# Test1.net
KiCad netlist of a schematic drawn in Altium Designer
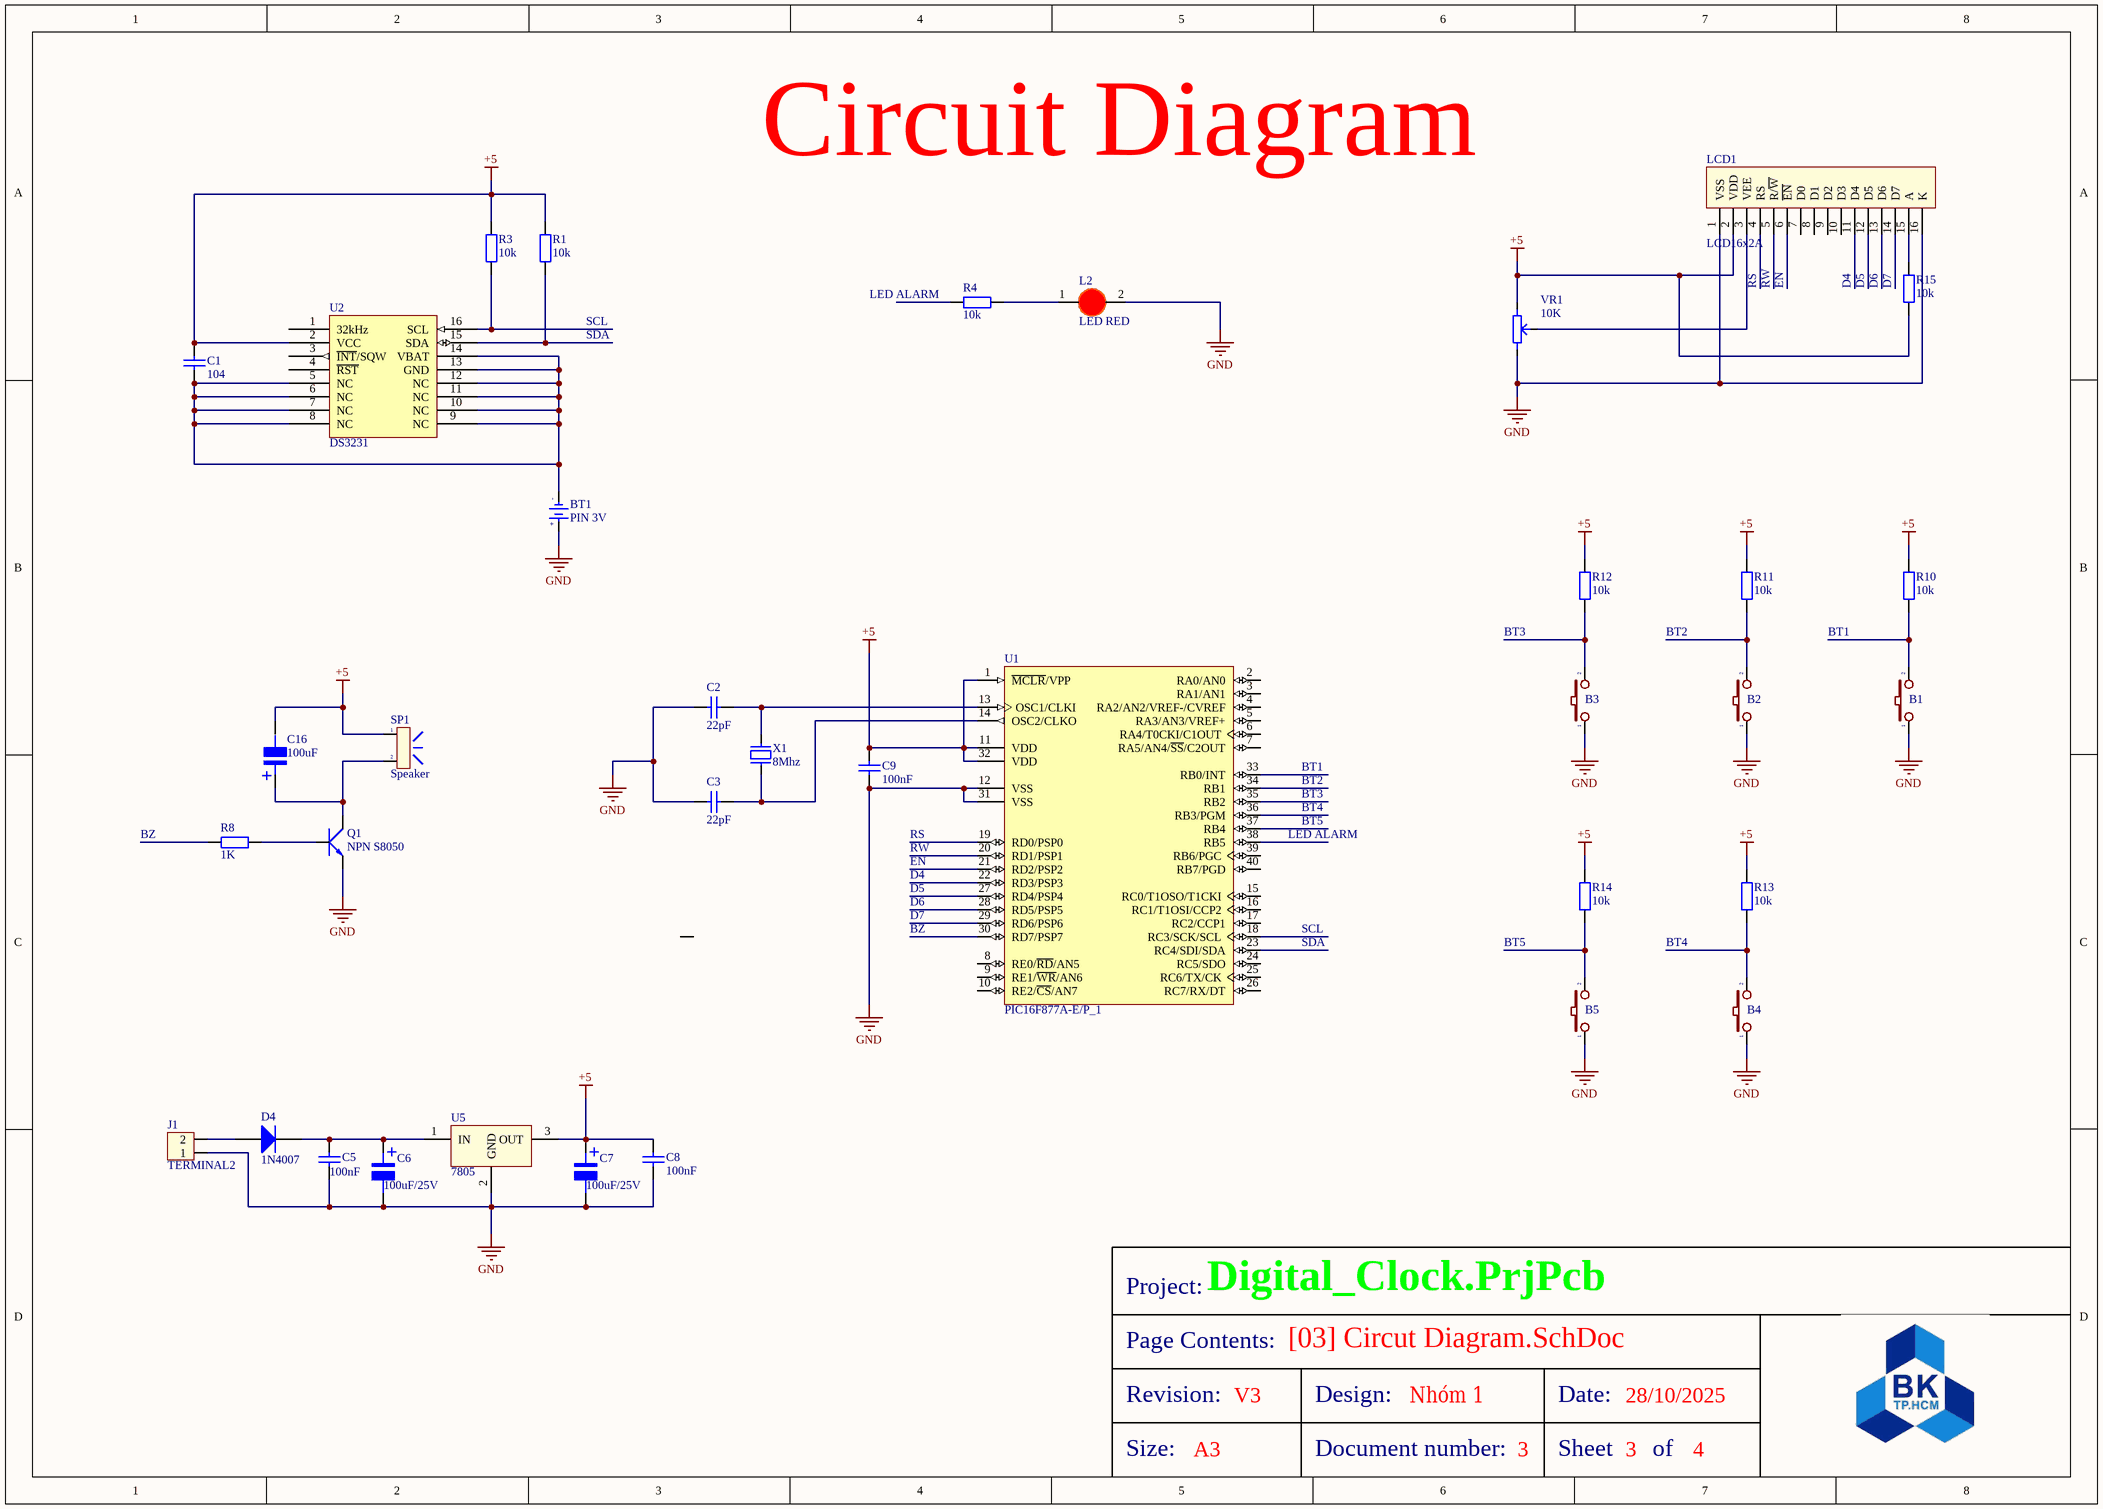
[diagram p0: Test1.SchDoc]

(export (version "E")
  (design (tool "Eeschema 10.0.6"))
  (components
    (comp (ref "B1")
      (value "~")
      (footprint "SW2")
      (description "Switch button 2 pin")
      (libsource (lib "syhaunguyen") (part "SW2"))
    )
    (comp (ref "B2")
      (value "~")
      (footprint "SW2")
      (description "Switch button 2 pin")
      (libsource (lib "syhaunguyen") (part "SW2"))
    )
    (comp (ref "B3")
      (value "~")
      (footprint "SW2")
      (description "Switch button 2 pin")
      (libsource (lib "syhaunguyen") (part "SW2"))
    )
    (comp (ref "B4")
      (value "~")
      (footprint "SW2")
      (description "Switch button 2 pin")
      (libsource (lib "syhaunguyen") (part "SW2"))
    )
    (comp (ref "B5")
      (value "~")
      (footprint "SW2")
      (description "Switch button 2 pin")
      (libsource (lib "syhaunguyen") (part "SW2"))
    )
    (comp (ref "BT1")
      (value "PIN 3V")
      (footprint "PIN3V")
      (description "Battery 3VDC")
      (libsource (lib "syhaunguyen") (part "PIN 3V"))
    )
    (comp (ref "C1")
      (value "104")
      (footprint "tu gom")
      (description "Cắm")
      (libsource (lib "Capacitor") (part "Tu gom 104 50V"))
    )
    (comp (ref "C2")
      (value "22pF")
      (footprint "tu gom")
      (description "Cắm")
      (libsource (lib "Capacitor") (part "Tu gom 22pF 50V"))
    )
    (comp (ref "C3")
      (value "22pF")
      (footprint "tu gom")
      (description "Cắm")
      (libsource (lib "Capacitor") (part "Tu gom 22pF 50V"))
    )
    (comp (ref "C5")
      (value "100nF")
      (footprint "tu gom")
      (description "Cắm")
      (libsource (lib "Capacitor") (part "Tu gom 22pF 50V"))
    )
    (comp (ref "C6")
      (value "100uF/25V")
      (footprint "tu nhom 10 (g)")
      (description "Dán")
      (libsource (lib "") (part "Tu Nhom 100uF 35V_1"))
    )
    (comp (ref "C7")
      (value "100uF/25V")
      (footprint "tu nhom 10 (g)")
      (description "Dán")
      (libsource (lib "") (part "Tu Nhom 100uF 35V_1"))
    )
    (comp (ref "C8")
      (value "100nF")
      (footprint "tu gom")
      (description "Cắm")
      (libsource (lib "Capacitor") (part "Tu gom 22pF 50V"))
    )
    (comp (ref "C9")
      (value "100nF")
      (footprint "tu gom")
      (description "Cắm")
      (libsource (lib "Capacitor") (part "Tu gom 22pF 50V"))
    )
    (comp (ref "C16")
      (value "100uF")
      (footprint "tu nhom 10 (g)")
      (description "Dán")
      (libsource (lib "Capacitor") (part "Tu Nhom 100uF 35V"))
    )
    (comp (ref "D4")
      (value "1N4007")
      (footprint "DIODE SOD-123")
      (description "Dán")
      (libsource (lib "Diode") (part "Diode S4"))
    )
    (comp (ref "J1")
      (value "TERMINAL2")
      (footprint "Header 2P DC 2.54")
      (description "Cắm")
      (libsource (lib "Header") (part "Header 2P 2.54 Duc Cong"))
    )
    (comp (ref "L2")
      (value "LED RED")
      (footprint "LED-5MM-RED")
      (description "Cắm")
      (libsource (lib "Led") (part "LED 5mm Do"))
    )
    (comp (ref "LCD1")
      (value "LCD16x2A")
      (footprint "LCD16X2")
      (description "LCD dipslay 16 char, 2 line")
      (libsource (lib "syhaunguyen") (part "LCD16x2"))
    )
    (comp (ref "Q1")
      (value "NPN S8050")
      (footprint "QTO-92")
      (description "P 600mW, ECB")
      (libsource (lib "syhaunguyen") (part "NPN_ECB"))
    )
    (comp (ref "R1")
      (value "10k")
      (footprint "tro smd 0603")
      (description "Dán")
      (libsource (lib "Resistor") (part "Tro 0603 5% 10k"))
    )
    (comp (ref "R3")
      (value "10k")
      (footprint "tro smd 0603")
      (description "Dán")
      (libsource (lib "Resistor") (part "Tro 0603 5% 10k"))
    )
    (comp (ref "R4")
      (value "10k")
      (footprint "tro smd 0603")
      (description "Dán")
      (libsource (lib "Resistor") (part "Tro 0603 5% 10k"))
    )
    (comp (ref "R8")
      (value "1K")
      (footprint "tro smd 0603")
      (description "Dán")
      (libsource (lib "Resistor") (part "Tro 0603 5% 10k"))
    )
    (comp (ref "R10")
      (value "10k")
      (footprint "tro smd 0603")
      (description "Dán")
      (libsource (lib "Resistor") (part "Tro 0603 5% 10k"))
    )
    (comp (ref "R11")
      (value "10k")
      (footprint "tro smd 0603")
      (description "Dán")
      (libsource (lib "Resistor") (part "Tro 0603 5% 10k"))
    )
    (comp (ref "R12")
      (value "10k")
      (footprint "tro smd 0603")
      (description "Dán")
      (libsource (lib "Resistor") (part "Tro 0603 5% 10k"))
    )
    (comp (ref "R13")
      (value "10k")
      (footprint "tro smd 0603")
      (description "Dán")
      (libsource (lib "Resistor") (part "Tro 0603 5% 10k"))
    )
    (comp (ref "R14")
      (value "10k")
      (footprint "tro smd 0603")
      (description "Dán")
      (libsource (lib "Resistor") (part "Tro 0603 5% 10k"))
    )
    (comp (ref "R15")
      (value "10k")
      (footprint "tro smd 0603")
      (description "Dán")
      (libsource (lib "Resistor") (part "Tro 0603 5% 10k"))
    )
    (comp (ref "SP1")
      (value "Speaker")
      (footprint "SPK")
      (description "Speaker Chip")
      (libsource (lib "syhaunguyen") (part "SPK"))
    )
    (comp (ref "U1")
      (value "PIC16F877A-E/P_1")
      (footprint "PDIP600-P40")
      (fields (field (name "PUBLISHER") "Altium Limited"))
      (libsource (lib "Cty1") (part "PIC16F877A-E/P_1"))
    )
    (comp (ref "U2") (value "DS3231") (footprint "SL3016") (libsource (lib "My Library") (part "DS3231")))
    (comp (ref "U5")
      (value "7805")
      (footprint "QTO-220")
      (description "On ap +, from + 5 to + 24VDC")
      (libsource (lib "syhaunguyen") (part "LM78xx"))
    )
    (comp (ref "VR1")
      (value "10K")
      (footprint "Bien Tro Tam Giac Dung")
      (description "Cắm")
      (libsource (lib "Resistor") (part "Bien tro tam giac 10K Dung"))
    )
    (comp (ref "X1")
      (value "8Mhz")
      (footprint "XT2")
      (description "Crystal For all Crystal 2pin.")
      (libsource (lib "syhaunguyen") (part "XT2"))
    )
  )
  (nets
    (net (code "1") (name "+5") (class "Default")
      (node (ref "C1") (pin "1") (pinfunction "1_1") (pintype "passive"))
      (node (ref "C16") (pin "2") (pinfunction "2_2") (pintype "passive"))
      (node (ref "C7") (pin "1") (pinfunction "1_1") (pintype "passive"))
      (node (ref "C8") (pin "1") (pinfunction "1_1") (pintype "passive"))
      (node (ref "C9") (pin "1") (pinfunction "1_1") (pintype "passive"))
      (node (ref "LCD1") (pin "2") (pinfunction "VDD_2") (pintype "passive"))
      (node (ref "R1") (pin "2") (pinfunction "2_2") (pintype "passive"))
      (node (ref "R10") (pin "1") (pinfunction "1_1") (pintype "passive"))
      (node (ref "R11") (pin "1") (pinfunction "1_1") (pintype "passive"))
      (node (ref "R12") (pin "1") (pinfunction "1_1") (pintype "passive"))
      (node (ref "R13") (pin "1") (pinfunction "1_1") (pintype "passive"))
      (node (ref "R14") (pin "1") (pinfunction "1_1") (pintype "passive"))
      (node (ref "R15") (pin "1") (pinfunction "1_1") (pintype "passive"))
      (node (ref "R3") (pin "2") (pinfunction "2_2") (pintype "passive"))
      (node (ref "SP1") (pin "1") (pinfunction "1_1") (pintype "passive"))
      (node (ref "U1") (pin "1") (pinfunction "~{MCLR}/VPP_1") (pintype "input"))
      (node (ref "U1") (pin "11") (pinfunction "VDD_11") (pintype "power_in"))
      (node (ref "U1") (pin "32") (pinfunction "VDD_32") (pintype "power_in"))
      (node (ref "U2") (pin "2") (pinfunction "VCC_2") (pintype "passive"))
      (node (ref "U5") (pin "3") (pinfunction "OUT_3") (pintype "passive"))
      (node (ref "VR1") (pin "1") (pinfunction "1_1") (pintype "passive"))
    )
    (net (code "2") (name "GND") (class "Default")
      (node (ref "B1") (pin "1") (pinfunction "1_1") (pintype "passive"))
      (node (ref "B2") (pin "1") (pinfunction "1_1") (pintype "passive"))
      (node (ref "B3") (pin "1") (pinfunction "1_1") (pintype "passive"))
      (node (ref "B4") (pin "1") (pinfunction "1_1") (pintype "passive"))
      (node (ref "B5") (pin "1") (pinfunction "1_1") (pintype "passive"))
      (node (ref "BT1") (pin "1") (pinfunction "+3V_1") (pintype "passive"))
      (node (ref "C2") (pin "2") (pinfunction "2_2") (pintype "passive"))
      (node (ref "C3") (pin "2") (pinfunction "2_2") (pintype "passive"))
      (node (ref "C5") (pin "2") (pinfunction "2_2") (pintype "passive"))
      (node (ref "C6") (pin "2") (pinfunction "2_2") (pintype "passive"))
      (node (ref "C7") (pin "2") (pinfunction "2_2") (pintype "passive"))
      (node (ref "C8") (pin "2") (pinfunction "2_2") (pintype "passive"))
      (node (ref "C9") (pin "2") (pinfunction "2_2") (pintype "passive"))
      (node (ref "J1") (pin "1") (pinfunction "1_1") (pintype "passive"))
      (node (ref "L2") (pin "2") (pinfunction "K_2") (pintype "passive"))
      (node (ref "LCD1") (pin "1") (pinfunction "VSS_1") (pintype "passive"))
      (node (ref "LCD1") (pin "16") (pinfunction "K_16") (pintype "passive"))
      (node (ref "Q1") (pin "1") (pinfunction "E_1") (pintype "passive"))
      (node (ref "U1") (pin "12") (pinfunction "VSS_12") (pintype "power_in"))
      (node (ref "U1") (pin "31") (pinfunction "VSS_31") (pintype "power_in"))
      (node (ref "U5") (pin "2") (pinfunction "GND_2") (pintype "passive"))
      (node (ref "VR1") (pin "3") (pinfunction "3_3") (pintype "passive"))
    )
    (net (code "3") (name "Net-(B1-Pad2)") (class "Default")
      (node (ref "B1") (pin "2") (pinfunction "2_2") (pintype "passive"))
      (node (ref "R10") (pin "2") (pinfunction "2_2") (pintype "passive"))
    )
    (net (code "4") (name "Net-(B2-Pad2)") (class "Default")
      (node (ref "B2") (pin "2") (pinfunction "2_2") (pintype "passive"))
      (node (ref "R11") (pin "2") (pinfunction "2_2") (pintype "passive"))
    )
    (net (code "5") (name "Net-(B3-Pad2)") (class "Default")
      (node (ref "B3") (pin "2") (pinfunction "2_2") (pintype "passive"))
      (node (ref "R12") (pin "2") (pinfunction "2_2") (pintype "passive"))
    )
    (net (code "6") (name "Net-(B4-Pad2)") (class "Default")
      (node (ref "B4") (pin "2") (pinfunction "2_2") (pintype "passive"))
      (node (ref "R13") (pin "2") (pinfunction "2_2") (pintype "passive"))
    )
    (net (code "7") (name "Net-(B5-Pad2)") (class "Default")
      (node (ref "B5") (pin "2") (pinfunction "2_2") (pintype "passive"))
      (node (ref "R14") (pin "2") (pinfunction "2_2") (pintype "passive"))
    )
    (net (code "8") (name "Net-(BT1-GND)") (class "Default")
      (node (ref "BT1") (pin "2") (pinfunction "GND_2") (pintype "passive"))
      (node (ref "C1") (pin "2") (pinfunction "2_2") (pintype "passive"))
      (node (ref "U2") (pin "10") (pinfunction "NC_10") (pintype "passive"))
      (node (ref "U2") (pin "11") (pinfunction "NC_11") (pintype "passive"))
      (node (ref "U2") (pin "12") (pinfunction "NC_12") (pintype "passive"))
      (node (ref "U2") (pin "13") (pinfunction "GND_13") (pintype "passive"))
      (node (ref "U2") (pin "14") (pinfunction "VBAT_14") (pintype "passive"))
      (node (ref "U2") (pin "5") (pinfunction "NC_5") (pintype "passive"))
      (node (ref "U2") (pin "6") (pinfunction "NC_6") (pintype "passive"))
      (node (ref "U2") (pin "7") (pinfunction "NC_7") (pintype "passive"))
      (node (ref "U2") (pin "8") (pinfunction "NC_8") (pintype "passive"))
      (node (ref "U2") (pin "9") (pinfunction "NC_9") (pintype "passive"))
    )
    (net (code "9") (name "Net-(D4-A)") (class "Default")
      (node (ref "D4") (pin "1") (pinfunction "A_1") (pintype "passive"))
      (node (ref "J1") (pin "2") (pinfunction "2_2") (pintype "passive"))
    )
    (net (code "10") (name "Net-(D4-K)") (class "Default")
      (node (ref "C5") (pin "1") (pinfunction "1_1") (pintype "passive"))
      (node (ref "C6") (pin "1") (pinfunction "1_1") (pintype "passive"))
      (node (ref "D4") (pin "2") (pinfunction "K_2") (pintype "passive"))
      (node (ref "U5") (pin "1") (pinfunction "IN_1") (pintype "passive"))
    )
    (net (code "11") (name "Net-(L2-A)") (class "Default")
      (node (ref "L2") (pin "1") (pinfunction "A_1") (pintype "passive"))
      (node (ref "R4") (pin "2") (pinfunction "2_2") (pintype "passive"))
    )
    (net (code "12") (name "Net-(LCD1-A)") (class "Default")
      (node (ref "LCD1") (pin "15") (pinfunction "A_15") (pintype "passive"))
      (node (ref "R15") (pin "2") (pinfunction "2_2") (pintype "passive"))
    )
    (net (code "13") (name "Net-(LCD1-VEE)") (class "Default")
      (node (ref "LCD1") (pin "3") (pinfunction "VEE_3") (pintype "passive"))
      (node (ref "VR1") (pin "2") (pinfunction "2_2") (pintype "passive"))
    )
    (net (code "14") (name "Net-(Q1-B)") (class "Default")
      (node (ref "Q1") (pin "3") (pinfunction "B_3") (pintype "passive"))
      (node (ref "R8") (pin "2") (pinfunction "2_2") (pintype "passive"))
    )
    (net (code "15") (name "Net-(Q1-C)") (class "Default")
      (node (ref "C16") (pin "1") (pinfunction "1_1") (pintype "passive"))
      (node (ref "Q1") (pin "2") (pinfunction "C_2") (pintype "passive"))
      (node (ref "SP1") (pin "2") (pinfunction "2_2") (pintype "passive"))
    )
    (net (code "16") (name "Net-(U1-OSC1{slash}CLKI)") (class "Default")
      (node (ref "C2") (pin "1") (pinfunction "1_1") (pintype "passive"))
      (node (ref "U1") (pin "13") (pinfunction "OSC1/CLKI_13") (pintype "input"))
      (node (ref "X1") (pin "1") (pinfunction "1_1") (pintype "passive"))
    )
    (net (code "17") (name "Net-(U1-OSC2{slash}CLKO)") (class "Default")
      (node (ref "C3") (pin "1") (pinfunction "1_1") (pintype "passive"))
      (node (ref "U1") (pin "14") (pinfunction "OSC2/CLKO_14") (pintype "output"))
      (node (ref "X1") (pin "2") (pinfunction "2_2") (pintype "passive"))
    )
    (net (code "18") (name "Net-(U2-SCL)") (class "Default")
      (node (ref "R3") (pin "1") (pinfunction "1_1") (pintype "passive"))
      (node (ref "U2") (pin "16") (pinfunction "SCL_16") (pintype "input"))
    )
    (net (code "19") (name "Net-(U2-SDA)") (class "Default")
      (node (ref "R1") (pin "1") (pinfunction "1_1") (pintype "passive"))
      (node (ref "U2") (pin "15") (pinfunction "SDA_15") (pintype "bidirectional"))
    )
    (net (code "20") (name "unconnected-(LCD1-D0-Pad7)") (class "Default")
      (node (ref "LCD1") (pin "7") (pinfunction "D0_7") (pintype "passive"))
    )
    (net (code "21") (name "unconnected-(LCD1-D1-Pad8)") (class "Default")
      (node (ref "LCD1") (pin "8") (pinfunction "D1_8") (pintype "passive"))
    )
    (net (code "22") (name "unconnected-(LCD1-D2-Pad9)") (class "Default")
      (node (ref "LCD1") (pin "9") (pinfunction "D2_9") (pintype "passive"))
    )
    (net (code "23") (name "unconnected-(LCD1-D3-Pad10)") (class "Default")
      (node (ref "LCD1") (pin "10") (pinfunction "D3_10") (pintype "passive"))
    )
    (net (code "24") (name "unconnected-(LCD1-D4-Pad11)") (class "Default")
      (node (ref "LCD1") (pin "11") (pinfunction "D4_11") (pintype "passive"))
    )
    (net (code "25") (name "unconnected-(LCD1-D5-Pad12)") (class "Default")
      (node (ref "LCD1") (pin "12") (pinfunction "D5_12") (pintype "passive"))
    )
    (net (code "26") (name "unconnected-(LCD1-D6-Pad13)") (class "Default")
      (node (ref "LCD1") (pin "13") (pinfunction "D6_13") (pintype "passive"))
    )
    (net (code "27") (name "unconnected-(LCD1-D7-Pad14)") (class "Default")
      (node (ref "LCD1") (pin "14") (pinfunction "D7_14") (pintype "passive"))
    )
    (net (code "28") (name "unconnected-(LCD1-RS-Pad4)") (class "Default")
      (node (ref "LCD1") (pin "4") (pinfunction "RS_4") (pintype "passive"))
    )
    (net (code "29") (name "unconnected-(LCD1-R{slash}~{W}-Pad5)") (class "Default")
      (node (ref "LCD1") (pin "5") (pinfunction "R/~{W}_5") (pintype "passive"))
    )
    (net (code "30") (name "unconnected-(LCD1-~{EN}-Pad6)") (class "Default")
      (node (ref "LCD1") (pin "6") (pinfunction "~{EN}_6") (pintype "passive"))
    )
    (net (code "31") (name "unconnected-(R4-Pad1)") (class "Default")
      (node (ref "R4") (pin "1") (pinfunction "1_1") (pintype "passive"))
    )
    (net (code "32") (name "unconnected-(R8-Pad1)") (class "Default")
      (node (ref "R8") (pin "1") (pinfunction "1_1") (pintype "passive"))
    )
    (net (code "33") (name "unconnected-(U1-RA0{slash}AN0-Pad2)") (class "Default")
      (node (ref "U1") (pin "2") (pinfunction "RA0/AN0_2") (pintype "bidirectional"))
    )
    (net (code "34") (name "unconnected-(U1-RA1{slash}AN1-Pad3)") (class "Default")
      (node (ref "U1") (pin "3") (pinfunction "RA1/AN1_3") (pintype "bidirectional"))
    )
    (net (code "35") (name "unconnected-(U1-RA2{slash}AN2{slash}VREF-{slash}CVREF-Pad4)") (class "Default")
      (node (ref "U1") (pin "4") (pinfunction "RA2/AN2/VREF-/CVREF_4") (pintype "bidirectional"))
    )
    (net (code "36") (name "unconnected-(U1-RA3{slash}AN3{slash}VREF+-Pad5)") (class "Default")
      (node (ref "U1") (pin "5") (pinfunction "RA3/AN3/VREF+_5") (pintype "bidirectional"))
    )
    (net (code "37") (name "unconnected-(U1-RA4{slash}T0CKI{slash}C1OUT-Pad6)") (class "Default")
      (node (ref "U1") (pin "6") (pinfunction "RA4/T0CKI/C1OUT_6") (pintype "bidirectional"))
    )
    (net (code "38") (name "unconnected-(U1-RA5{slash}AN4{slash}~{SS}{slash}C2OUT-Pad7)") (class "Default")
      (node (ref "U1") (pin "7") (pinfunction "RA5/AN4/~{SS}/C2OUT_7") (pintype "bidirectional"))
    )
    (net (code "39") (name "unconnected-(U1-RB0{slash}INT-Pad33)") (class "Default")
      (node (ref "U1") (pin "33") (pinfunction "RB0/INT_33") (pintype "bidirectional"))
    )
    (net (code "40") (name "unconnected-(U1-RB1-Pad34)") (class "Default")
      (node (ref "U1") (pin "34") (pinfunction "RB1_34") (pintype "bidirectional"))
    )
    (net (code "41") (name "unconnected-(U1-RB2-Pad35)") (class "Default")
      (node (ref "U1") (pin "35") (pinfunction "RB2_35") (pintype "bidirectional"))
    )
    (net (code "42") (name "unconnected-(U1-RB3{slash}PGM-Pad36)") (class "Default")
      (node (ref "U1") (pin "36") (pinfunction "RB3/PGM_36") (pintype "bidirectional"))
    )
    (net (code "43") (name "unconnected-(U1-RB4-Pad37)") (class "Default")
      (node (ref "U1") (pin "37") (pinfunction "RB4_37") (pintype "bidirectional"))
    )
    (net (code "44") (name "unconnected-(U1-RB5-Pad38)") (class "Default")
      (node (ref "U1") (pin "38") (pinfunction "RB5_38") (pintype "bidirectional"))
    )
    (net (code "45") (name "unconnected-(U1-RB6{slash}PGC-Pad39)") (class "Default")
      (node (ref "U1") (pin "39") (pinfunction "RB6/PGC_39") (pintype "bidirectional"))
    )
    (net (code "46") (name "unconnected-(U1-RB7{slash}PGD-Pad40)") (class "Default")
      (node (ref "U1") (pin "40") (pinfunction "RB7/PGD_40") (pintype "bidirectional"))
    )
    (net (code "47") (name "unconnected-(U1-RC0{slash}T1OSO{slash}T1CKI-Pad15)") (class "Default")
      (node (ref "U1") (pin "15") (pinfunction "RC0/T1OSO/T1CKI_15") (pintype "bidirectional"))
    )
    (net (code "48") (name "unconnected-(U1-RC1{slash}T1OSI{slash}CCP2-Pad16)") (class "Default")
      (node (ref "U1") (pin "16") (pinfunction "RC1/T1OSI/CCP2_16") (pintype "bidirectional"))
    )
    (net (code "49") (name "unconnected-(U1-RC2{slash}CCP1-Pad17)") (class "Default")
      (node (ref "U1") (pin "17") (pinfunction "RC2/CCP1_17") (pintype "bidirectional"))
    )
    (net (code "50") (name "unconnected-(U1-RC3{slash}SCK{slash}SCL-Pad18)") (class "Default")
      (node (ref "U1") (pin "18") (pinfunction "RC3/SCK/SCL_18") (pintype "bidirectional"))
    )
    (net (code "51") (name "unconnected-(U1-RC4{slash}SDI{slash}SDA-Pad23)") (class "Default")
      (node (ref "U1") (pin "23") (pinfunction "RC4/SDI/SDA_23") (pintype "bidirectional"))
    )
    (net (code "52") (name "unconnected-(U1-RC5{slash}SDO-Pad24)") (class "Default")
      (node (ref "U1") (pin "24") (pinfunction "RC5/SDO_24") (pintype "bidirectional"))
    )
    (net (code "53") (name "unconnected-(U1-RC6{slash}TX{slash}CK-Pad25)") (class "Default")
      (node (ref "U1") (pin "25") (pinfunction "RC6/TX/CK_25") (pintype "bidirectional"))
    )
    (net (code "54") (name "unconnected-(U1-RC7{slash}RX{slash}DT-Pad26)") (class "Default")
      (node (ref "U1") (pin "26") (pinfunction "RC7/RX/DT_26") (pintype "bidirectional"))
    )
    (net (code "55") (name "unconnected-(U1-RD0{slash}PSP0-Pad19)") (class "Default")
      (node (ref "U1") (pin "19") (pinfunction "RD0/PSP0_19") (pintype "bidirectional"))
    )
    (net (code "56") (name "unconnected-(U1-RD1{slash}PSP1-Pad20)") (class "Default")
      (node (ref "U1") (pin "20") (pinfunction "RD1/PSP1_20") (pintype "bidirectional"))
    )
    (net (code "57") (name "unconnected-(U1-RD2{slash}PSP2-Pad21)") (class "Default")
      (node (ref "U1") (pin "21") (pinfunction "RD2/PSP2_21") (pintype "bidirectional"))
    )
    (net (code "58") (name "unconnected-(U1-RD3{slash}PSP3-Pad22)") (class "Default")
      (node (ref "U1") (pin "22") (pinfunction "RD3/PSP3_22") (pintype "bidirectional"))
    )
    (net (code "59") (name "unconnected-(U1-RD4{slash}PSP4-Pad27)") (class "Default")
      (node (ref "U1") (pin "27") (pinfunction "RD4/PSP4_27") (pintype "bidirectional"))
    )
    (net (code "60") (name "unconnected-(U1-RD5{slash}PSP5-Pad28)") (class "Default")
      (node (ref "U1") (pin "28") (pinfunction "RD5/PSP5_28") (pintype "bidirectional"))
    )
    (net (code "61") (name "unconnected-(U1-RD6{slash}PSP6-Pad29)") (class "Default")
      (node (ref "U1") (pin "29") (pinfunction "RD6/PSP6_29") (pintype "bidirectional"))
    )
    (net (code "62") (name "unconnected-(U1-RD7{slash}PSP7-Pad30)") (class "Default")
      (node (ref "U1") (pin "30") (pinfunction "RD7/PSP7_30") (pintype "bidirectional"))
    )
    (net (code "63") (name "unconnected-(U1-RE0{slash}~{RD}{slash}AN5-Pad8)") (class "Default")
      (node (ref "U1") (pin "8") (pinfunction "RE0/~{RD}/AN5_8") (pintype "bidirectional"))
    )
    (net (code "64") (name "unconnected-(U1-RE1{slash}~{WR}{slash}AN6-Pad9)") (class "Default")
      (node (ref "U1") (pin "9") (pinfunction "RE1/~{WR}/AN6_9") (pintype "bidirectional"))
    )
    (net (code "65") (name "unconnected-(U1-RE2{slash}~{CS}{slash}AN7-Pad10)") (class "Default")
      (node (ref "U1") (pin "10") (pinfunction "RE2/~{CS}/AN7_10") (pintype "bidirectional"))
    )
    (net (code "66") (name "unconnected-(U2-32kHz-Pad1)") (class "Default")
      (node (ref "U2") (pin "1") (pinfunction "32kHz_1") (pintype "passive"))
    )
    (net (code "67") (name "unconnected-(U2-~{INT}{slash}SQW-Pad3)") (class "Default")
      (node (ref "U2") (pin "3") (pinfunction "~{INT}/SQW_3") (pintype "output"))
    )
    (net (code "68") (name "unconnected-(U2-~{RST}-Pad4)") (class "Default")
      (node (ref "U2") (pin "4") (pinfunction "~{RST}_4") (pintype "passive"))
    )
  )
)
